# Balancing_v1.net
KiCad netlist of a schematic drawn in EAGLE
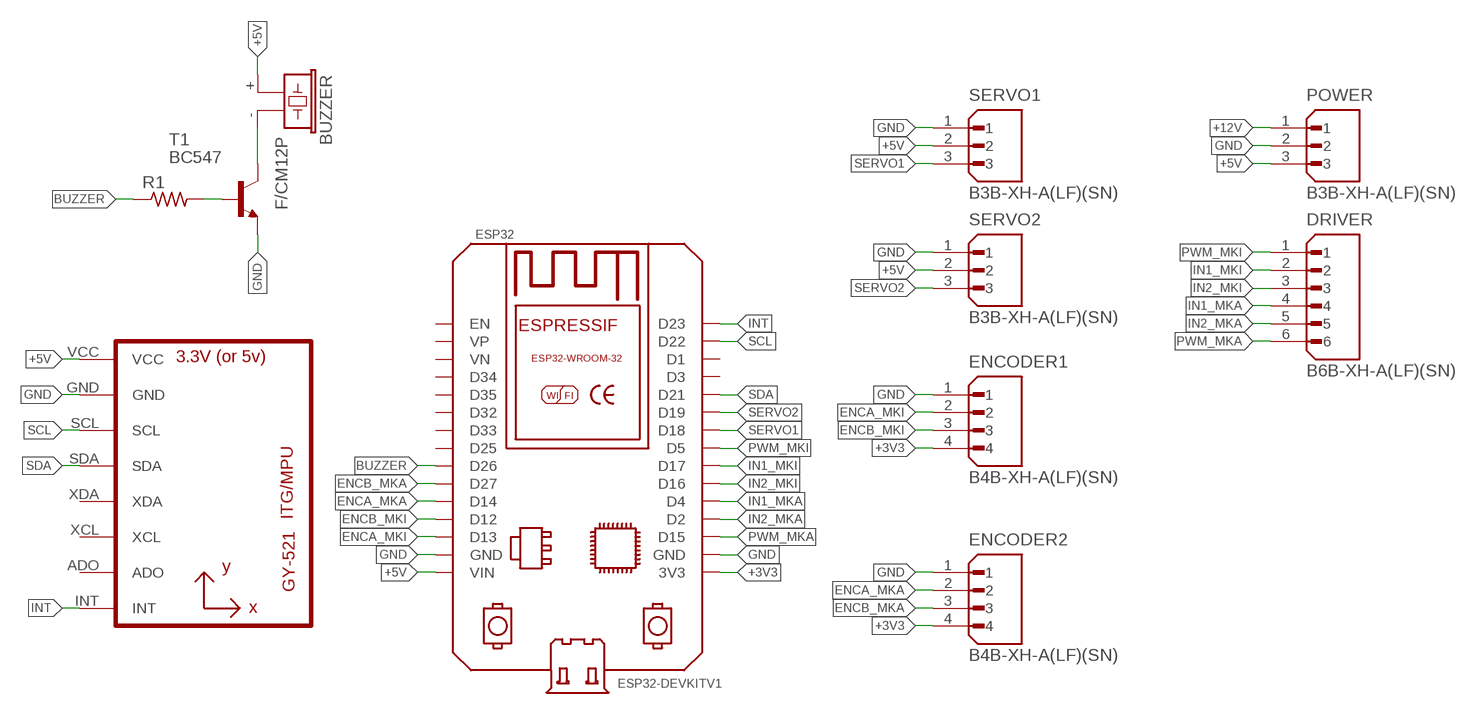
[diagram p0: schematic, sheet 1]

(export (version "E")
  (design (tool "Eeschema 10.0.6"))
  (components
    (comp (ref "BUZZER")
      (value "F/CM12P")
      (footprint "eagle-import:F_CM12P")
      (libsource (lib "eagle-import") (part "F/CM12P"))
    )
    (comp (ref "DRIVER")
      (value "B6B-XH-A(LF)(SN)")
      (footprint "eagle-import:JST_B6B-XH-A(LF)(SN)")
      (fields (field (name "MF") "JST Sales"))
      (libsource (lib "eagle-import") (part "B6B-XH-A(LF)(SN)"))
    )
    (comp (ref "ENCODER1")
      (value "B4B-XH-A(LF)(SN)")
      (footprint "eagle-import:JST_B4B-XH-A(LF)(SN)")
      (fields (field (name "MF") "JST") (field (name "MP") "B4B-XH-A  (LF)(SN)"))
      (libsource (lib "eagle-import") (part "B4B-XH-A(LF)(SN)"))
    )
    (comp (ref "ENCODER2")
      (value "B4B-XH-A(LF)(SN)")
      (footprint "eagle-import:JST_B4B-XH-A(LF)(SN)")
      (fields (field (name "MF") "JST") (field (name "MP") "B4B-XH-A  (LF)(SN)"))
      (libsource (lib "eagle-import") (part "B4B-XH-A(LF)(SN)"))
    )
    (comp (ref "ESP32")
      (value "ESP32DEVKITV1")
      (footprint "eagle-import:ESP32-DEVKITV1")
      (libsource (lib "eagle-import") (part "ESP32DEVKITV1"))
    )
    (comp (ref "POWER")
      (value "B3B-XH-A(LF)(SN)")
      (footprint "eagle-import:JST_B3B-XH-A(LF)(SN)")
      (fields (field (name "MF") "JST Sales America Inc.") (field (name "MP") "B3B-XH-A (LF)(SN)"))
      (libsource (lib "eagle-import") (part "B3B-XH-A(LF)(SN)"))
    )
    (comp (ref "R1")
      (value "R-US_0204/7")
      (footprint "eagle-import:0204_7")
      (libsource (lib "eagle-import") (part "R-US_0204/7"))
    )
    (comp (ref "SERVO1")
      (value "B3B-XH-A(LF)(SN)")
      (footprint "eagle-import:JST_B3B-XH-A(LF)(SN)")
      (fields (field (name "MF") "JST Sales America Inc.") (field (name "MP") "B3B-XH-A (LF)(SN)"))
      (libsource (lib "eagle-import") (part "B3B-XH-A(LF)(SN)"))
    )
    (comp (ref "SERVO2")
      (value "B3B-XH-A(LF)(SN)")
      (footprint "eagle-import:JST_B3B-XH-A(LF)(SN)")
      (fields (field (name "MF") "JST Sales America Inc.") (field (name "MP") "B3B-XH-A (LF)(SN)"))
      (libsource (lib "eagle-import") (part "B3B-XH-A(LF)(SN)"))
    )
    (comp (ref "T1")
      (value "BC547")
      (footprint "eagle-import:TO92")
      (libsource (lib "eagle-import") (part "BC547"))
    )
    (comp (ref "U1")
      (value "GY-521MPU6050")
      (footprint "eagle-import:GY-521")
      (libsource (lib "eagle-import") (part "GY-521MPU6050"))
    )
  )
  (nets
    (net (code "1") (name "+3V3") (class "Default")
      (node (ref "ENCODER1") (pin "4") (pinfunction "4_4") (pintype "passive"))
      (node (ref "ENCODER2") (pin "4") (pinfunction "4_4") (pintype "passive"))
      (node (ref "ESP32") (pin "3V3") (pinfunction "3V3_3V3") (pintype "bidirectional"))
    )
    (net (code "2") (name "+5V") (class "Default")
      (node (ref "BUZZER") (pin "+") (pinfunction "1_+") (pintype "passive"))
      (node (ref "ESP32") (pin "VIN") (pinfunction "VIN_VIN") (pintype "bidirectional"))
      (node (ref "POWER") (pin "3") (pinfunction "3_3") (pintype "passive"))
      (node (ref "SERVO1") (pin "2") (pinfunction "2_2") (pintype "passive"))
      (node (ref "SERVO2") (pin "2") (pinfunction "2_2") (pintype "passive"))
      (node (ref "U1") (pin "VCC") (pinfunction "VCC_VCC") (pintype "bidirectional"))
    )
    (net (code "3") (name "+12V") (class "Default")
      (node (ref "POWER") (pin "1") (pinfunction "1_1") (pintype "passive"))
    )
    (net (code "4") (name "BUZZER") (class "Default")
      (node (ref "ESP32") (pin "D26") (pinfunction "D26_D26") (pintype "bidirectional"))
      (node (ref "R1") (pin "1") (pinfunction "1_1") (pintype "passive"))
    )
    (net (code "5") (name "ENCA_MKA") (class "Default")
      (node (ref "ENCODER2") (pin "2") (pinfunction "2_2") (pintype "passive"))
      (node (ref "ESP32") (pin "D14") (pinfunction "D14_D14") (pintype "bidirectional"))
    )
    (net (code "6") (name "ENCA_MKI") (class "Default")
      (node (ref "ENCODER1") (pin "2") (pinfunction "2_2") (pintype "passive"))
      (node (ref "ESP32") (pin "D13") (pinfunction "D13_D13") (pintype "bidirectional"))
    )
    (net (code "7") (name "ENCB_MKA") (class "Default")
      (node (ref "ENCODER2") (pin "3") (pinfunction "3_3") (pintype "passive"))
      (node (ref "ESP32") (pin "D27") (pinfunction "D27_D27") (pintype "bidirectional"))
    )
    (net (code "8") (name "ENCB_MKI") (class "Default")
      (node (ref "ENCODER1") (pin "3") (pinfunction "3_3") (pintype "passive"))
      (node (ref "ESP32") (pin "D12") (pinfunction "D12_D12") (pintype "bidirectional"))
    )
    (net (code "9") (name "GND") (class "Default")
      (node (ref "ENCODER1") (pin "1") (pinfunction "1_1") (pintype "passive"))
      (node (ref "ENCODER2") (pin "1") (pinfunction "1_1") (pintype "passive"))
      (node (ref "ESP32") (pin "GND") (pinfunction "GND_GND") (pintype "bidirectional"))
      (node (ref "ESP32") (pin "GND@1") (pinfunction "GND_GND@1") (pintype "bidirectional"))
      (node (ref "POWER") (pin "2") (pinfunction "2_2") (pintype "passive"))
      (node (ref "SERVO1") (pin "1") (pinfunction "1_1") (pintype "passive"))
      (node (ref "SERVO2") (pin "1") (pinfunction "1_1") (pintype "passive"))
      (node (ref "T1") (pin "1") (pinfunction "E_1") (pintype "passive"))
      (node (ref "U1") (pin "GND") (pinfunction "GND_GND") (pintype "bidirectional"))
    )
    (net (code "10") (name "IN1_MKA") (class "Default")
      (node (ref "DRIVER") (pin "4") (pinfunction "4_4") (pintype "passive"))
      (node (ref "ESP32") (pin "D4") (pinfunction "D4_D4") (pintype "bidirectional"))
    )
    (net (code "11") (name "IN1_MKI") (class "Default")
      (node (ref "DRIVER") (pin "2") (pinfunction "2_2") (pintype "passive"))
      (node (ref "ESP32") (pin "D17") (pinfunction "D17_D17") (pintype "bidirectional"))
    )
    (net (code "12") (name "IN2_MKA") (class "Default")
      (node (ref "DRIVER") (pin "5") (pinfunction "5_5") (pintype "passive"))
      (node (ref "ESP32") (pin "D2") (pinfunction "D2_D2") (pintype "bidirectional"))
    )
    (net (code "13") (name "IN2_MKI") (class "Default")
      (node (ref "DRIVER") (pin "3") (pinfunction "3_3") (pintype "passive"))
      (node (ref "ESP32") (pin "D16") (pinfunction "D16_D16") (pintype "bidirectional"))
    )
    (net (code "14") (name "INT") (class "Default")
      (node (ref "ESP32") (pin "D23") (pinfunction "D23_D23") (pintype "bidirectional"))
      (node (ref "U1") (pin "INT") (pinfunction "INT_INT") (pintype "bidirectional"))
    )
    (net (code "15") (name "Net-(BUZZER-2)") (class "Default")
      (node (ref "BUZZER") (pin "-") (pinfunction "2_-") (pintype "passive"))
      (node (ref "T1") (pin "3") (pinfunction "C_3") (pintype "passive"))
    )
    (net (code "16") (name "Net-(T1-B)") (class "Default")
      (node (ref "R1") (pin "2") (pinfunction "2_2") (pintype "passive"))
      (node (ref "T1") (pin "2") (pinfunction "B_2") (pintype "passive"))
    )
    (net (code "17") (name "PWM_MKA") (class "Default")
      (node (ref "DRIVER") (pin "6") (pinfunction "6_6") (pintype "passive"))
      (node (ref "ESP32") (pin "D15") (pinfunction "D15_D15") (pintype "bidirectional"))
    )
    (net (code "18") (name "PWM_MKI") (class "Default")
      (node (ref "DRIVER") (pin "1") (pinfunction "1_1") (pintype "passive"))
      (node (ref "ESP32") (pin "D5") (pinfunction "D5_D5") (pintype "bidirectional"))
    )
    (net (code "19") (name "SCL") (class "Default")
      (node (ref "ESP32") (pin "D22") (pinfunction "D22_D22") (pintype "bidirectional"))
      (node (ref "U1") (pin "SCL") (pinfunction "SCL_SCL") (pintype "bidirectional"))
    )
    (net (code "20") (name "SDA") (class "Default")
      (node (ref "ESP32") (pin "D21") (pinfunction "D21_D21") (pintype "bidirectional"))
      (node (ref "U1") (pin "SDA") (pinfunction "SDA_SDA") (pintype "bidirectional"))
    )
    (net (code "21") (name "SERVO1") (class "Default")
      (node (ref "ESP32") (pin "D18") (pinfunction "D18_D18") (pintype "bidirectional"))
      (node (ref "SERVO1") (pin "3") (pinfunction "3_3") (pintype "passive"))
    )
    (net (code "22") (name "SERVO2") (class "Default")
      (node (ref "ESP32") (pin "D19") (pinfunction "D19_D19") (pintype "bidirectional"))
      (node (ref "SERVO2") (pin "3") (pinfunction "3_3") (pintype "passive"))
    )
    (net (code "23") (name "unconnected-(ESP32-PadD1)") (class "Default")
      (node (ref "ESP32") (pin "D1") (pinfunction "D1_D1") (pintype "bidirectional"))
    )
    (net (code "24") (name "unconnected-(ESP32-PadD3)") (class "Default")
      (node (ref "ESP32") (pin "D3") (pinfunction "D3_D3") (pintype "bidirectional"))
    )
    (net (code "25") (name "unconnected-(ESP32-PadD25)") (class "Default")
      (node (ref "ESP32") (pin "D25") (pinfunction "D25_D25") (pintype "bidirectional"))
    )
    (net (code "26") (name "unconnected-(ESP32-PadD32)") (class "Default")
      (node (ref "ESP32") (pin "D32") (pinfunction "D32_D32") (pintype "bidirectional"))
    )
    (net (code "27") (name "unconnected-(ESP32-PadD33)") (class "Default")
      (node (ref "ESP32") (pin "D33") (pinfunction "D33_D33") (pintype "bidirectional"))
    )
    (net (code "28") (name "unconnected-(ESP32-PadD34)") (class "Default")
      (node (ref "ESP32") (pin "D34") (pinfunction "D34_D34") (pintype "bidirectional"))
    )
    (net (code "29") (name "unconnected-(ESP32-PadD35)") (class "Default")
      (node (ref "ESP32") (pin "D35") (pinfunction "D35_D35") (pintype "bidirectional"))
    )
    (net (code "30") (name "unconnected-(ESP32-PadEN)") (class "Default")
      (node (ref "ESP32") (pin "EN") (pinfunction "EN_EN") (pintype "bidirectional"))
    )
    (net (code "31") (name "unconnected-(ESP32-PadVN)") (class "Default")
      (node (ref "ESP32") (pin "VN") (pinfunction "VN_VN") (pintype "bidirectional"))
    )
    (net (code "32") (name "unconnected-(ESP32-PadVP)") (class "Default")
      (node (ref "ESP32") (pin "VP") (pinfunction "VP_VP") (pintype "bidirectional"))
    )
    (net (code "33") (name "unconnected-(U1-PadADO)") (class "Default")
      (node (ref "U1") (pin "ADO") (pinfunction "ADO_ADO") (pintype "bidirectional"))
    )
    (net (code "34") (name "unconnected-(U1-PadXCL)") (class "Default")
      (node (ref "U1") (pin "XCL") (pinfunction "XCL_XCL") (pintype "bidirectional"))
    )
    (net (code "35") (name "unconnected-(U1-PadXDA)") (class "Default")
      (node (ref "U1") (pin "XDA") (pinfunction "XDA_XDA") (pintype "bidirectional"))
    )
  )
)
